# 3transistor.net
KiCad netlist of a schematic drawn in EAGLE
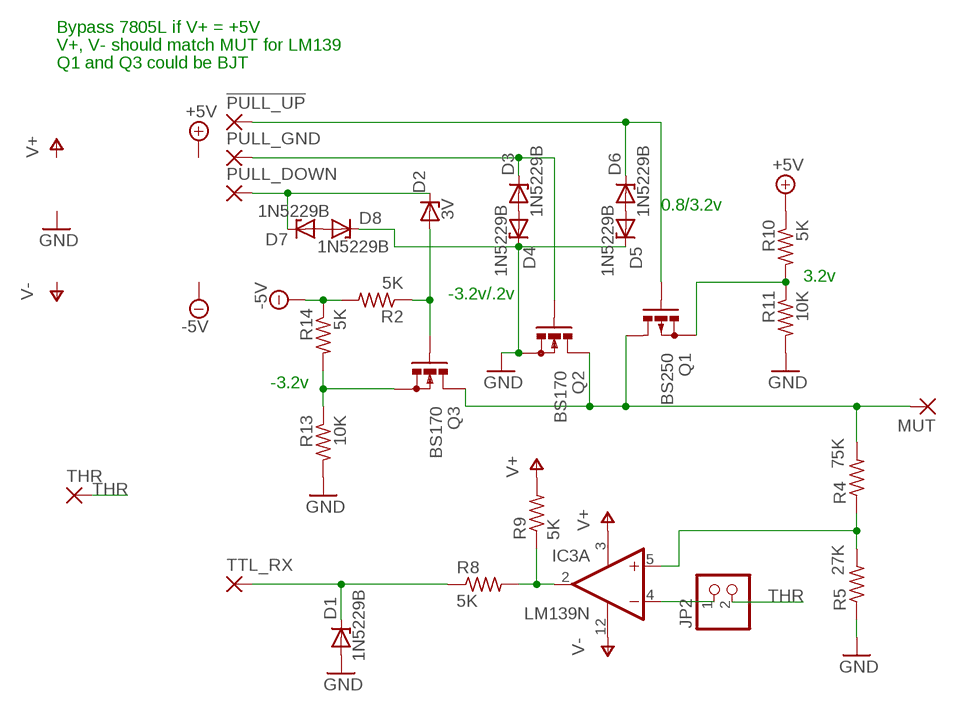
[diagram p0: schematic, sheet 1]

(export (version "E")
  (design (tool "Eeschema 10.0.6"))
  (components
    (comp (ref "!PULL_UP")
      (value "1,6/0,9")
      (footprint "eagle-import:1,6_0,9")
      (libsource (lib "eagle-import") (part "1,6/0,9"))
    )
    (comp (ref "D1")
      (value "1N5229B")
      (footprint "eagle-import:ZDIO-2.5")
      (libsource (lib "eagle-import") (part "ZENER-DIODEZD-2.5"))
    )
    (comp (ref "D2")
      (value "3V")
      (footprint "eagle-import:ZDIO-2.5")
      (libsource (lib "eagle-import") (part "ZENER-DIODEZD-2.5"))
    )
    (comp (ref "D3")
      (value "1N5229B")
      (footprint "eagle-import:ZDIO-2.5")
      (libsource (lib "eagle-import") (part "ZENER-DIODEZD-2.5"))
    )
    (comp (ref "D4")
      (value "1N5229B")
      (footprint "eagle-import:ZDIO-2.5")
      (libsource (lib "eagle-import") (part "ZENER-DIODEZD-2.5"))
    )
    (comp (ref "D5")
      (value "1N5229B")
      (footprint "eagle-import:ZDIO-2.5")
      (libsource (lib "eagle-import") (part "ZENER-DIODEZD-2.5"))
    )
    (comp (ref "D6")
      (value "1N5229B")
      (footprint "eagle-import:ZDIO-2.5")
      (libsource (lib "eagle-import") (part "ZENER-DIODEZD-2.5"))
    )
    (comp (ref "D7")
      (value "1N5229B")
      (footprint "eagle-import:ZDIO-2.5")
      (libsource (lib "eagle-import") (part "ZENER-DIODEZD-2.5"))
    )
    (comp (ref "D8")
      (value "1N5229B")
      (footprint "eagle-import:ZDIO-2.5")
      (libsource (lib "eagle-import") (part "ZENER-DIODEZD-2.5"))
    )
    (comp (ref "IC3")
      (value "LM139N")
      (footprint "eagle-import:DIL14")
      (libsource (lib "eagle-import") (part "LM339N"))
    )
    (comp (ref "JP2")
      (value "PINHD-1X2")
      (footprint "eagle-import:1X02")
      (libsource (lib "eagle-import") (part "PINHD-1X2"))
    )
    (comp (ref "MUT")
      (value "1,6/0,9")
      (footprint "eagle-import:1,6_0,9")
      (libsource (lib "eagle-import") (part "1,6/0,9"))
    )
    (comp (ref "PULL_DOWN")
      (value "1,6/0,9")
      (footprint "eagle-import:1,6_0,9")
      (libsource (lib "eagle-import") (part "1,6/0,9"))
    )
    (comp (ref "PULL_GND")
      (value "1,6/0,9")
      (footprint "eagle-import:1,6_0,9")
      (libsource (lib "eagle-import") (part "1,6/0,9"))
    )
    (comp (ref "Q1")
      (value "BS250")
      (footprint "eagle-import:SOT54E")
      (libsource (lib "eagle-import") (part "BS250"))
    )
    (comp (ref "Q2")
      (value "BS170")
      (footprint "eagle-import:SOT54E")
      (libsource (lib "eagle-import") (part "BS170"))
    )
    (comp (ref "Q3")
      (value "BS170")
      (footprint "eagle-import:SOT54E")
      (libsource (lib "eagle-import") (part "BS170"))
    )
    (comp (ref "R2")
      (value "5K")
      (footprint "eagle-import:0207_2V")
      (libsource (lib "eagle-import") (part "R-US_0207/2V"))
    )
    (comp (ref "R4")
      (value "75K")
      (footprint "eagle-import:0207_2V")
      (libsource (lib "eagle-import") (part "R-US_0207/2V"))
    )
    (comp (ref "R5")
      (value "27K")
      (footprint "eagle-import:0207_2V")
      (libsource (lib "eagle-import") (part "R-US_0207/2V"))
    )
    (comp (ref "R8")
      (value "5K")
      (footprint "eagle-import:0207_2V")
      (libsource (lib "eagle-import") (part "R-US_0207/2V"))
    )
    (comp (ref "R9")
      (value "5K")
      (footprint "eagle-import:0207_2V")
      (libsource (lib "eagle-import") (part "R-US_0207/2V"))
    )
    (comp (ref "R10")
      (value "5K")
      (footprint "eagle-import:0207_2V")
      (libsource (lib "eagle-import") (part "R-US_0207/2V"))
    )
    (comp (ref "R11")
      (value "10K")
      (footprint "eagle-import:0207_2V")
      (libsource (lib "eagle-import") (part "R-US_0207/2V"))
    )
    (comp (ref "R13")
      (value "10K")
      (footprint "eagle-import:0207_2V")
      (libsource (lib "eagle-import") (part "R-US_0207/2V"))
    )
    (comp (ref "R14")
      (value "5K")
      (footprint "eagle-import:0207_2V")
      (libsource (lib "eagle-import") (part "R-US_0207/2V"))
    )
    (comp (ref "THR")
      (value "1,6/0,9")
      (footprint "eagle-import:1,6_0,9")
      (libsource (lib "eagle-import") (part "1,6/0,9"))
    )
    (comp (ref "TTL_RX")
      (value "1,6/0,9")
      (footprint "eagle-import:1,6_0,9")
      (libsource (lib "eagle-import") (part "1,6/0,9"))
    )
  )
  (nets
    (net (code "1") (name "+5V") (class "Default")
      (node (ref "R10") (pin "1") (pinfunction "1_1") (pintype "passive"))
    )
    (net (code "2") (name "-5V") (class "Default")
      (node (ref "R14") (pin "1") (pinfunction "1_1") (pintype "passive"))
      (node (ref "R2") (pin "2") (pinfunction "2_2") (pintype "passive"))
    )
    (net (code "3") (name "/THR") (class "Default")
      (node (ref "JP2") (pin "2") (pinfunction "2_2") (pintype "passive"))
      (node (ref "THR") (pin "1") (pinfunction "P_1") (pintype "passive"))
    )
    (net (code "4") (name "GND") (class "Default")
      (node (ref "D1") (pin "A") (pinfunction "A_A") (pintype "passive"))
      (node (ref "D4") (pin "C") (pinfunction "C_C") (pintype "passive"))
      (node (ref "D5") (pin "C") (pinfunction "C_C") (pintype "passive"))
      (node (ref "D8") (pin "C") (pinfunction "C_C") (pintype "passive"))
      (node (ref "Q2") (pin "S") (pinfunction "S_S") (pintype "passive"))
      (node (ref "R11") (pin "2") (pinfunction "2_2") (pintype "passive"))
      (node (ref "R13") (pin "2") (pinfunction "2_2") (pintype "passive"))
      (node (ref "R5") (pin "1") (pinfunction "1_1") (pintype "passive"))
    )
    (net (code "5") (name "Net-(!PULL_UP-P)") (class "Default")
      (node (ref "!PULL_UP") (pin "1") (pinfunction "P_1") (pintype "passive"))
      (node (ref "D6") (pin "C") (pinfunction "C_C") (pintype "passive"))
      (node (ref "Q1") (pin "G") (pinfunction "G_G") (pintype "passive"))
    )
    (net (code "6") (name "Net-(D2-PadA)") (class "Default")
      (node (ref "D2") (pin "A") (pinfunction "A_A") (pintype "passive"))
      (node (ref "Q3") (pin "G") (pinfunction "G_G") (pintype "passive"))
      (node (ref "R2") (pin "1") (pinfunction "1_1") (pintype "passive"))
    )
    (net (code "7") (name "Net-(D3-PadA)") (class "Default")
      (node (ref "D3") (pin "A") (pinfunction "A_A") (pintype "passive"))
      (node (ref "D4") (pin "A") (pinfunction "A_A") (pintype "passive"))
    )
    (net (code "8") (name "Net-(D5-PadA)") (class "Default")
      (node (ref "D5") (pin "A") (pinfunction "A_A") (pintype "passive"))
      (node (ref "D6") (pin "A") (pinfunction "A_A") (pintype "passive"))
    )
    (net (code "9") (name "Net-(D7-PadA)") (class "Default")
      (node (ref "D7") (pin "A") (pinfunction "A_A") (pintype "passive"))
      (node (ref "D8") (pin "A") (pinfunction "A_A") (pintype "passive"))
    )
    (net (code "10") (name "Net-(IC3A-+IN)") (class "Default")
      (node (ref "IC3") (pin "5") (pinfunction "+IN_5") (pintype "input"))
      (node (ref "R4") (pin "1") (pinfunction "1_1") (pintype "passive"))
      (node (ref "R5") (pin "2") (pinfunction "2_2") (pintype "passive"))
    )
    (net (code "11") (name "Net-(IC3A--IN)") (class "Default")
      (node (ref "IC3") (pin "4") (pinfunction "-IN_4") (pintype "input"))
      (node (ref "JP2") (pin "1") (pinfunction "1_1") (pintype "passive"))
    )
    (net (code "12") (name "Net-(IC3A-OUT)") (class "Default")
      (node (ref "IC3") (pin "2") (pinfunction "OUT_2") (pintype "open_collector"))
      (node (ref "R8") (pin "2") (pinfunction "2_2") (pintype "passive"))
      (node (ref "R9") (pin "1") (pinfunction "1_1") (pintype "passive"))
    )
    (net (code "13") (name "Net-(MUT-P)") (class "Default")
      (node (ref "MUT") (pin "1") (pinfunction "P_1") (pintype "passive"))
      (node (ref "Q1") (pin "D") (pinfunction "D_D") (pintype "passive"))
      (node (ref "Q2") (pin "D") (pinfunction "D_D") (pintype "passive"))
      (node (ref "Q3") (pin "D") (pinfunction "D_D") (pintype "passive"))
      (node (ref "R4") (pin "2") (pinfunction "2_2") (pintype "passive"))
    )
    (net (code "14") (name "Net-(PULL_DOWN-P)") (class "Default")
      (node (ref "D2") (pin "C") (pinfunction "C_C") (pintype "passive"))
      (node (ref "D7") (pin "C") (pinfunction "C_C") (pintype "passive"))
      (node (ref "PULL_DOWN") (pin "1") (pinfunction "P_1") (pintype "passive"))
    )
    (net (code "15") (name "Net-(PULL_GND-P)") (class "Default")
      (node (ref "D3") (pin "C") (pinfunction "C_C") (pintype "passive"))
      (node (ref "PULL_GND") (pin "1") (pinfunction "P_1") (pintype "passive"))
      (node (ref "Q2") (pin "G") (pinfunction "G_G") (pintype "passive"))
    )
    (net (code "16") (name "Net-(Q1-PadS)") (class "Default")
      (node (ref "Q1") (pin "S") (pinfunction "S_S") (pintype "passive"))
      (node (ref "R10") (pin "2") (pinfunction "2_2") (pintype "passive"))
      (node (ref "R11") (pin "1") (pinfunction "1_1") (pintype "passive"))
    )
    (net (code "17") (name "Net-(Q3-PadS)") (class "Default")
      (node (ref "Q3") (pin "S") (pinfunction "S_S") (pintype "passive"))
      (node (ref "R13") (pin "1") (pinfunction "1_1") (pintype "passive"))
      (node (ref "R14") (pin "2") (pinfunction "2_2") (pintype "passive"))
    )
    (net (code "18") (name "Net-(TTL_RX-P)") (class "Default")
      (node (ref "D1") (pin "C") (pinfunction "C_C") (pintype "passive"))
      (node (ref "R8") (pin "1") (pinfunction "1_1") (pintype "passive"))
      (node (ref "TTL_RX") (pin "1") (pinfunction "P_1") (pintype "passive"))
    )
    (net (code "19") (name "V+") (class "Default")
      (node (ref "IC3") (pin "3") (pinfunction "V+_3") (pintype "power_in"))
      (node (ref "R9") (pin "2") (pinfunction "2_2") (pintype "passive"))
    )
    (net (code "20") (name "V-") (class "Default")
      (node (ref "IC3") (pin "12") (pinfunction "GND_12") (pintype "power_in"))
    )
  )
)
